# W5500_ETH-SPI.net
KiCad netlist of a schematic drawn in Altium Designer
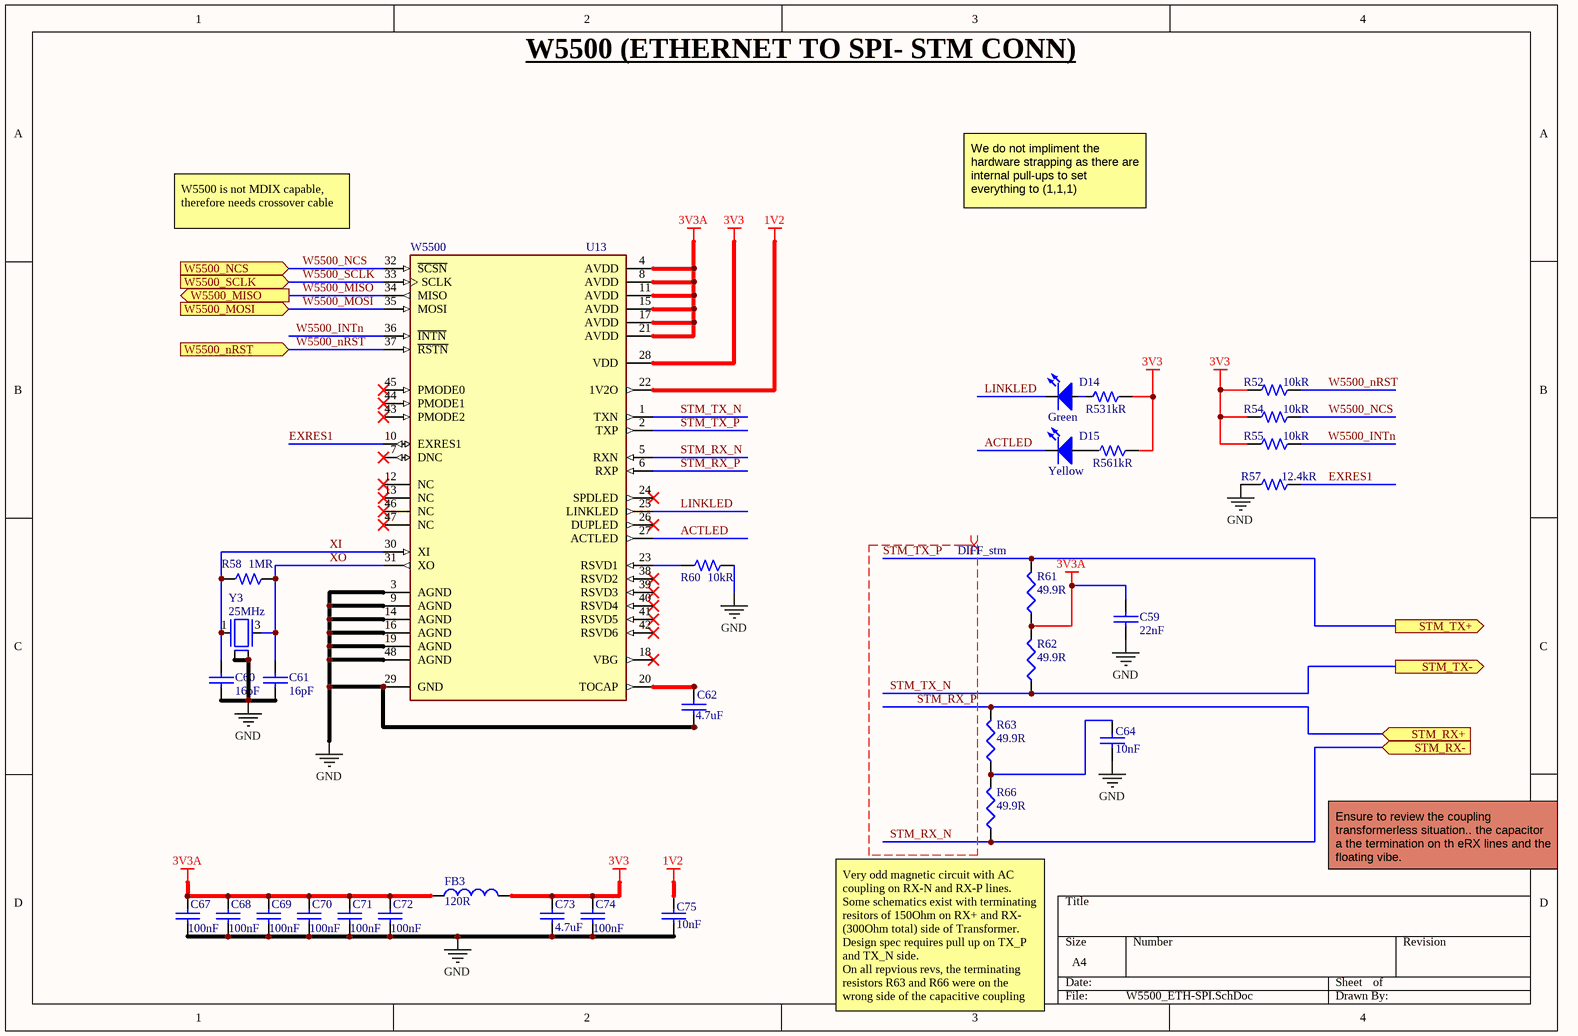
[diagram p0: W5500_ETH-SPI.SchDoc]

(export (version "E")
  (design (tool "Eeschema 10.0.6"))
  (components
    (comp (ref "C59")
      (value "Capacitor")
      (footprint "CAP0402")
      (fields (field (name "CAPACITANCE") "22nF"))
      (libsource (lib "") (part "Capacitor_1"))
    )
    (comp (ref "C60")
      (value "Capacitor")
      (footprint "CAP0402")
      (fields (field (name "CAPACITANCE") "16pF"))
      (libsource (lib "BPL-ShematicLibrary") (part "Capacitor"))
    )
    (comp (ref "C61")
      (value "Capacitor")
      (footprint "CAP0402")
      (fields (field (name "CAPACITANCE") "16pF"))
      (libsource (lib "BPL-ShematicLibrary") (part "Capacitor"))
    )
    (comp (ref "C62")
      (value "Capacitor")
      (footprint "CAP0402")
      (fields (field (name "CAPACITANCE") "4.7uF"))
      (libsource (lib "BPL-ShematicLibrary") (part "Capacitor"))
    )
    (comp (ref "C64")
      (value "Capacitor")
      (footprint "CAP0402")
      (fields (field (name "CAPACITANCE") "10nF"))
      (libsource (lib "") (part "Capacitor_1"))
    )
    (comp (ref "C67")
      (value "Capacitor")
      (footprint "CAP0402")
      (fields
        (field (name "MANUFACTURER") "TDK")
        (field (name "MANUFACTURER PART NUMBER") "CGA2B3X7R1H104K050BB")
        (field (name "CAPACITANCE") "100nF")
        (field (name "TOLERANCE") "10%")
      )
      (libsource (lib "BPL-ShematicLibrary") (part "Capacitor"))
    )
    (comp (ref "C68")
      (value "Capacitor")
      (footprint "CAP0402")
      (fields
        (field (name "MANUFACTURER") "TDK")
        (field (name "MANUFACTURER PART NUMBER") "CGA2B3X7R1H104K050BB")
        (field (name "CAPACITANCE") "100nF")
        (field (name "TOLERANCE") "10%")
      )
      (libsource (lib "BPL-ShematicLibrary") (part "Capacitor"))
    )
    (comp (ref "C69")
      (value "Capacitor")
      (footprint "CAP0402")
      (fields
        (field (name "MANUFACTURER") "TDK")
        (field (name "MANUFACTURER PART NUMBER") "CGA2B3X7R1H104K050BB")
        (field (name "CAPACITANCE") "100nF")
        (field (name "TOLERANCE") "10%")
      )
      (libsource (lib "BPL-ShematicLibrary") (part "Capacitor"))
    )
    (comp (ref "C70")
      (value "Capacitor")
      (footprint "CAP0402")
      (fields
        (field (name "MANUFACTURER") "TDK")
        (field (name "MANUFACTURER PART NUMBER") "CGA2B3X7R1H104K050BB")
        (field (name "CAPACITANCE") "100nF")
        (field (name "TOLERANCE") "10%")
      )
      (libsource (lib "BPL-ShematicLibrary") (part "Capacitor"))
    )
    (comp (ref "C71")
      (value "Capacitor")
      (footprint "CAP0402")
      (fields
        (field (name "MANUFACTURER") "TDK")
        (field (name "MANUFACTURER PART NUMBER") "CGA2B3X7R1H104K050BB")
        (field (name "CAPACITANCE") "100nF")
        (field (name "TOLERANCE") "10%")
      )
      (libsource (lib "BPL-ShematicLibrary") (part "Capacitor"))
    )
    (comp (ref "C72")
      (value "Capacitor")
      (footprint "CAP0402")
      (fields
        (field (name "MANUFACTURER") "TDK")
        (field (name "MANUFACTURER PART NUMBER") "CGA2B3X7R1H104K050BB")
        (field (name "CAPACITANCE") "100nF")
        (field (name "TOLERANCE") "10%")
      )
      (libsource (lib "BPL-ShematicLibrary") (part "Capacitor"))
    )
    (comp (ref "C73")
      (value "Capacitor")
      (footprint "CAP0402")
      (fields (field (name "CAPACITANCE") "4.7uF"))
      (libsource (lib "BPL-ShematicLibrary") (part "Capacitor"))
    )
    (comp (ref "C74")
      (value "Capacitor")
      (footprint "CAP0402")
      (fields
        (field (name "MANUFACTURER") "TDK")
        (field (name "MANUFACTURER PART NUMBER") "CGA2B3X7R1H104K050BB")
        (field (name "CAPACITANCE") "100nF")
        (field (name "TOLERANCE") "10%")
      )
      (libsource (lib "BPL-ShematicLibrary") (part "Capacitor"))
    )
    (comp (ref "C75")
      (value "Capacitor")
      (footprint "CAP0402")
      (fields (field (name "CAPACITANCE") "10nF"))
      (libsource (lib "") (part "Capacitor_1"))
    )
    (comp (ref "D14")
      (value "LED")
      (footprint "LED-0603-GREEN")
      (fields (field (name "COLOR") "Green"))
      (libsource (lib "BPL-ShematicLibrary") (part "LED"))
    )
    (comp (ref "D15")
      (value "LED")
      (footprint "LED-0603-YELLOW")
      (fields (field (name "COLOR") "Yellow"))
      (libsource (lib "BPL-ShematicLibrary") (part "LED"))
    )
    (comp (ref "FB3")
      (value "Ferrite Bead")
      (footprint "RES0402")
      (fields (field (name "TOLERANCE") "25%") (field (name "IMPEDANCE") "120R"))
      (libsource (lib "BPL-ShematicLibrary") (part "Ferrite Bead"))
    )
    (comp (ref "R52")
      (value "Resistor")
      (footprint "RES0402")
      (fields (field (name "RESISTANCE") "10kR") (field (name "TOLERANCE") "1%"))
      (libsource (lib "BPL-ShematicLibrary") (part "Resistor"))
    )
    (comp (ref "R53")
      (value "Resistor")
      (footprint "RES0402")
      (fields (field (name "TOLERANCE") "5%") (field (name "RESISTANCE") "1kR"))
      (libsource (lib "BPL-ShematicLibrary") (part "Resistor"))
    )
    (comp (ref "R54")
      (value "Resistor")
      (footprint "RES0402")
      (fields (field (name "RESISTANCE") "10kR") (field (name "TOLERANCE") "1%"))
      (libsource (lib "BPL-ShematicLibrary") (part "Resistor"))
    )
    (comp (ref "R55")
      (value "Resistor")
      (footprint "RES0402")
      (fields (field (name "RESISTANCE") "10kR") (field (name "TOLERANCE") "1%"))
      (libsource (lib "BPL-ShematicLibrary") (part "Resistor"))
    )
    (comp (ref "R56")
      (value "Resistor")
      (footprint "RES0402")
      (fields (field (name "TOLERANCE") "5%") (field (name "RESISTANCE") "1kR"))
      (libsource (lib "BPL-ShematicLibrary") (part "Resistor"))
    )
    (comp (ref "R57")
      (value "Resistor")
      (footprint "RES0402")
      (fields (field (name "RESISTANCE") "12.4kR") (field (name "TOLERANCE") "0.1%"))
      (libsource (lib "BPL-ShematicLibrary") (part "Resistor"))
    )
    (comp (ref "R58")
      (value "Resistor")
      (footprint "RES0402")
      (fields (field (name "RESISTANCE") "1MR") (field (name "TOLERANCE") "1%"))
      (libsource (lib "BPL-ShematicLibrary") (part "Resistor"))
    )
    (comp (ref "R60")
      (value "Resistor")
      (footprint "RES0402")
      (fields (field (name "RESISTANCE") "10kR") (field (name "TOLERANCE") "1%"))
      (libsource (lib "BPL-ShematicLibrary") (part "Resistor"))
    )
    (comp (ref "R61")
      (value "Res")
      (footprint "RES0402")
      (description "Resistor")
      (fields
        (field (name "MANUFACTURER") "Yageo")
        (field (name "MANUFACTURER PART NUMBER") "RC0402FR-0749R9L")
        (field (name "RESISTANCE") "49.9R")
      )
      (libsource (lib "") (part "Resistor_1"))
    )
    (comp (ref "R62")
      (value "Res")
      (footprint "RES0402")
      (description "Resistor")
      (fields
        (field (name "MANUFACTURER") "Yageo")
        (field (name "MANUFACTURER PART NUMBER") "RC0402FR-0749R9L")
        (field (name "RESISTANCE") "49.9R")
      )
      (libsource (lib "") (part "Resistor_1"))
    )
    (comp (ref "R63")
      (value "Res")
      (footprint "RES0402")
      (description "Resistor")
      (fields
        (field (name "MANUFACTURER") "Yageo")
        (field (name "MANUFACTURER PART NUMBER") "RC0402FR-0749R9L")
        (field (name "RESISTANCE") "49.9R")
      )
      (libsource (lib "") (part "Resistor_1"))
    )
    (comp (ref "R66")
      (value "Res")
      (footprint "RES0402")
      (description "Resistor")
      (fields
        (field (name "MANUFACTURER") "Yageo")
        (field (name "MANUFACTURER PART NUMBER") "RC0402FR-0749R9L")
        (field (name "RESISTANCE") "49.9R")
      )
      (libsource (lib "") (part "Resistor_1"))
    )
    (comp (ref "U13")
      (value "W5500_LQFP48")
      (footprint "LQFP-48, 7x7mm, 0.5mm pitch")
      (description "Ethernet to SPI MCU converter. Onboard TCP handling")
      (fields (field (name "MANUFACTURER PART NUMBER 1") "W5500"))
      (libsource (lib "BPL-ShematicLibrary") (part "W5500_LQFP48"))
    )
    (comp (ref "Y3")
      (value "Crystal_4Pin_ABM8G")
      (footprint "CRYSTAL_ABM8G")
      (fields (field (name "TOLERANCE") "30ppm") (field (name "FREQUENCY") "25MHz"))
      (libsource (lib "BPL-ShematicLibrary") (part "Crystal_4Pin_ABM8G"))
    )
  )
  (nets
    (net (code "1") (name "/ACTLED") (class "Default")
      (node (ref "D15") (pin "1") (pinfunction "1_1") (pintype "passive"))
      (node (ref "U13") (pin "27") (pinfunction "ACTLED_27") (pintype "output"))
    )
    (net (code "2") (name "/EXRES1") (class "Default")
      (node (ref "R57") (pin "1") (pinfunction "1_1") (pintype "passive"))
      (node (ref "U13") (pin "10") (pinfunction "EXRES1_10") (pintype "bidirectional"))
    )
    (net (code "3") (name "/LINKLED") (class "Default")
      (node (ref "D14") (pin "1") (pinfunction "1_1") (pintype "passive"))
      (node (ref "U13") (pin "25") (pinfunction "LINKLED_25") (pintype "output"))
    )
    (net (code "4") (name "/STM_RX_N") (class "Default")
      (node (ref "R66") (pin "1") (pinfunction "1_1") (pintype "passive"))
      (node (ref "U13") (pin "5") (pinfunction "RXN_5") (pintype "input"))
    )
    (net (code "5") (name "/STM_RX_P") (class "Default")
      (node (ref "R63") (pin "2") (pinfunction "2_2") (pintype "passive"))
      (node (ref "U13") (pin "6") (pinfunction "RXP_6") (pintype "input"))
    )
    (net (code "6") (name "/STM_TX_N") (class "Default")
      (node (ref "R62") (pin "1") (pinfunction "1_1") (pintype "passive"))
      (node (ref "U13") (pin "1") (pinfunction "TXN_1") (pintype "output"))
    )
    (net (code "7") (name "/STM_TX_P") (class "Default")
      (node (ref "R61") (pin "2") (pinfunction "2_2") (pintype "passive"))
      (node (ref "U13") (pin "2") (pinfunction "TXP_2") (pintype "output"))
    )
    (net (code "8") (name "/W5500_INTn") (class "Default")
      (node (ref "R55") (pin "1") (pinfunction "1_1") (pintype "passive"))
      (node (ref "U13") (pin "36") (pinfunction "~{INTN}_36") (pintype "input"))
    )
    (net (code "9") (name "/W5500_MISO") (class "Default")
      (node (ref "U13") (pin "34") (pinfunction "MISO_34") (pintype "output"))
    )
    (net (code "10") (name "/W5500_MOSI") (class "Default")
      (node (ref "U13") (pin "35") (pinfunction "MOSI_35") (pintype "input"))
    )
    (net (code "11") (name "/W5500_NCS") (class "Default")
      (node (ref "R54") (pin "1") (pinfunction "1_1") (pintype "passive"))
      (node (ref "U13") (pin "32") (pinfunction "~{SCSN}_32") (pintype "input"))
    )
    (net (code "12") (name "/W5500_SCLK") (class "Default")
      (node (ref "U13") (pin "33") (pinfunction "SCLK_33") (pintype "input"))
    )
    (net (code "13") (name "/W5500_nRST") (class "Default")
      (node (ref "R52") (pin "1") (pinfunction "1_1") (pintype "passive"))
      (node (ref "U13") (pin "37") (pinfunction "~{RSTN}_37") (pintype "input"))
    )
    (net (code "14") (name "/XI") (class "Default")
      (node (ref "C60") (pin "2") (pinfunction "2_2") (pintype "passive"))
      (node (ref "R58") (pin "1") (pinfunction "1_1") (pintype "passive"))
      (node (ref "U13") (pin "30") (pinfunction "XI_30") (pintype "input"))
      (node (ref "Y3") (pin "1") (pinfunction "Osc1_1") (pintype "passive"))
    )
    (net (code "15") (name "/XO") (class "Default")
      (node (ref "C61") (pin "2") (pinfunction "2_2") (pintype "passive"))
      (node (ref "R58") (pin "2") (pinfunction "2_2") (pintype "passive"))
      (node (ref "U13") (pin "31") (pinfunction "XO_31") (pintype "output"))
      (node (ref "Y3") (pin "3") (pinfunction "Osc2_3") (pintype "passive"))
    )
    (net (code "16") (name "1V2") (class "Default")
      (node (ref "C75") (pin "1") (pinfunction "1_1") (pintype "passive"))
      (node (ref "U13") (pin "22") (pinfunction "1V2O_22") (pintype "output"))
    )
    (net (code "17") (name "3V3") (class "Default")
      (node (ref "C73") (pin "1") (pinfunction "1_1") (pintype "passive"))
      (node (ref "C74") (pin "1") (pinfunction "1_1") (pintype "passive"))
      (node (ref "FB3") (pin "2") (pinfunction "2_2") (pintype "passive"))
      (node (ref "R52") (pin "2") (pinfunction "2_2") (pintype "passive"))
      (node (ref "R53") (pin "2") (pinfunction "2_2") (pintype "passive"))
      (node (ref "R54") (pin "2") (pinfunction "2_2") (pintype "passive"))
      (node (ref "R55") (pin "2") (pinfunction "2_2") (pintype "passive"))
      (node (ref "R56") (pin "2") (pinfunction "2_2") (pintype "passive"))
      (node (ref "U13") (pin "28") (pinfunction "VDD_28") (pintype "power_in"))
    )
    (net (code "18") (name "3V3A") (class "Default")
      (node (ref "C59") (pin "1") (pinfunction "1_1") (pintype "passive"))
      (node (ref "C67") (pin "1") (pinfunction "1_1") (pintype "passive"))
      (node (ref "C68") (pin "1") (pinfunction "1_1") (pintype "passive"))
      (node (ref "C69") (pin "1") (pinfunction "1_1") (pintype "passive"))
      (node (ref "C70") (pin "1") (pinfunction "1_1") (pintype "passive"))
      (node (ref "C71") (pin "1") (pinfunction "1_1") (pintype "passive"))
      (node (ref "C72") (pin "1") (pinfunction "1_1") (pintype "passive"))
      (node (ref "FB3") (pin "1") (pinfunction "1_1") (pintype "passive"))
      (node (ref "R61") (pin "1") (pinfunction "1_1") (pintype "passive"))
      (node (ref "R62") (pin "2") (pinfunction "2_2") (pintype "passive"))
      (node (ref "U13") (pin "11") (pinfunction "AVDD_11") (pintype "power_in"))
      (node (ref "U13") (pin "15") (pinfunction "AVDD_15") (pintype "power_in"))
      (node (ref "U13") (pin "17") (pinfunction "AVDD_17") (pintype "power_in"))
      (node (ref "U13") (pin "21") (pinfunction "AVDD_21") (pintype "power_in"))
      (node (ref "U13") (pin "4") (pinfunction "AVDD_4") (pintype "power_in"))
      (node (ref "U13") (pin "8") (pinfunction "AVDD_8") (pintype "power_in"))
    )
    (net (code "19") (name "GND") (class "Default")
      (node (ref "C59") (pin "2") (pinfunction "2_2") (pintype "passive"))
      (node (ref "C60") (pin "1") (pinfunction "1_1") (pintype "passive"))
      (node (ref "C61") (pin "1") (pinfunction "1_1") (pintype "passive"))
      (node (ref "C62") (pin "2") (pinfunction "2_2") (pintype "passive"))
      (node (ref "C64") (pin "2") (pinfunction "2_2") (pintype "passive"))
      (node (ref "C67") (pin "2") (pinfunction "2_2") (pintype "passive"))
      (node (ref "C68") (pin "2") (pinfunction "2_2") (pintype "passive"))
      (node (ref "C69") (pin "2") (pinfunction "2_2") (pintype "passive"))
      (node (ref "C70") (pin "2") (pinfunction "2_2") (pintype "passive"))
      (node (ref "C71") (pin "2") (pinfunction "2_2") (pintype "passive"))
      (node (ref "C72") (pin "2") (pinfunction "2_2") (pintype "passive"))
      (node (ref "C73") (pin "2") (pinfunction "2_2") (pintype "passive"))
      (node (ref "C74") (pin "2") (pinfunction "2_2") (pintype "passive"))
      (node (ref "C75") (pin "2") (pinfunction "2_2") (pintype "passive"))
      (node (ref "R57") (pin "2") (pinfunction "2_2") (pintype "passive"))
      (node (ref "R60") (pin "1") (pinfunction "1_1") (pintype "passive"))
      (node (ref "U13") (pin "14") (pinfunction "AGND_14") (pintype "power_in"))
      (node (ref "U13") (pin "16") (pinfunction "AGND_16") (pintype "power_in"))
      (node (ref "U13") (pin "19") (pinfunction "AGND_19") (pintype "power_in"))
      (node (ref "U13") (pin "29") (pinfunction "GND_29") (pintype "passive"))
      (node (ref "U13") (pin "3") (pinfunction "AGND_3") (pintype "power_in"))
      (node (ref "U13") (pin "48") (pinfunction "AGND_48") (pintype "power_in"))
      (node (ref "U13") (pin "9") (pinfunction "AGND_9") (pintype "power_in"))
      (node (ref "Y3") (pin "2") (pinfunction "GND_2") (pintype "power_in"))
      (node (ref "Y3") (pin "4") (pinfunction "GND_4") (pintype "power_in"))
    )
    (net (code "20") (name "Net-(C64-Pad1)") (class "Default")
      (node (ref "C64") (pin "1") (pinfunction "1_1") (pintype "passive"))
      (node (ref "R63") (pin "1") (pinfunction "1_1") (pintype "passive"))
      (node (ref "R66") (pin "2") (pinfunction "2_2") (pintype "passive"))
    )
    (net (code "21") (name "Net-(D14-Pad2)") (class "Default")
      (node (ref "D14") (pin "2") (pinfunction "2_2") (pintype "passive"))
      (node (ref "R53") (pin "1") (pinfunction "1_1") (pintype "passive"))
    )
    (net (code "22") (name "Net-(D15-Pad2)") (class "Default")
      (node (ref "D15") (pin "2") (pinfunction "2_2") (pintype "passive"))
      (node (ref "R56") (pin "1") (pinfunction "1_1") (pintype "passive"))
    )
    (net (code "23") (name "Net-(U13-RSVD1)") (class "Default")
      (node (ref "R60") (pin "2") (pinfunction "2_2") (pintype "passive"))
      (node (ref "U13") (pin "23") (pinfunction "RSVD1_23") (pintype "input"))
    )
    (net (code "24") (name "Net-(U13-TOCAP)") (class "Default")
      (node (ref "C62") (pin "1") (pinfunction "1_1") (pintype "passive"))
      (node (ref "U13") (pin "20") (pinfunction "TOCAP_20") (pintype "output"))
    )
    (net (code "25") (name "unconnected-(U13-DNC-Pad7)") (class "Default")
      (node (ref "U13") (pin "7") (pinfunction "DNC_7") (pintype "bidirectional+no_connect"))
    )
    (net (code "26") (name "unconnected-(U13-DUPLED-Pad26)") (class "Default")
      (node (ref "U13") (pin "26") (pinfunction "DUPLED_26") (pintype "output+no_connect"))
    )
    (net (code "27") (name "unconnected-(U13-NC-Pad12)") (class "Default")
      (node (ref "U13") (pin "12") (pinfunction "NC_12") (pintype "passive+no_connect"))
    )
    (net (code "28") (name "unconnected-(U13-NC-Pad13)") (class "Default")
      (node (ref "U13") (pin "13") (pinfunction "NC_13") (pintype "passive+no_connect"))
    )
    (net (code "29") (name "unconnected-(U13-NC-Pad46)") (class "Default")
      (node (ref "U13") (pin "46") (pinfunction "NC_46") (pintype "passive+no_connect"))
    )
    (net (code "30") (name "unconnected-(U13-NC-Pad47)") (class "Default")
      (node (ref "U13") (pin "47") (pinfunction "NC_47") (pintype "passive+no_connect"))
    )
    (net (code "31") (name "unconnected-(U13-PMODE0-Pad45)") (class "Default")
      (node (ref "U13") (pin "45") (pinfunction "PMODE0_45") (pintype "input+no_connect"))
    )
    (net (code "32") (name "unconnected-(U13-PMODE1-Pad44)") (class "Default")
      (node (ref "U13") (pin "44") (pinfunction "PMODE1_44") (pintype "input+no_connect"))
    )
    (net (code "33") (name "unconnected-(U13-PMODE2-Pad43)") (class "Default")
      (node (ref "U13") (pin "43") (pinfunction "PMODE2_43") (pintype "input+no_connect"))
    )
    (net (code "34") (name "unconnected-(U13-RSVD2-Pad38)") (class "Default")
      (node (ref "U13") (pin "38") (pinfunction "RSVD2_38") (pintype "input+no_connect"))
    )
    (net (code "35") (name "unconnected-(U13-RSVD3-Pad39)") (class "Default")
      (node (ref "U13") (pin "39") (pinfunction "RSVD3_39") (pintype "input+no_connect"))
    )
    (net (code "36") (name "unconnected-(U13-RSVD4-Pad40)") (class "Default")
      (node (ref "U13") (pin "40") (pinfunction "RSVD4_40") (pintype "input+no_connect"))
    )
    (net (code "37") (name "unconnected-(U13-RSVD5-Pad41)") (class "Default")
      (node (ref "U13") (pin "41") (pinfunction "RSVD5_41") (pintype "input+no_connect"))
    )
    (net (code "38") (name "unconnected-(U13-RSVD6-Pad42)") (class "Default")
      (node (ref "U13") (pin "42") (pinfunction "RSVD6_42") (pintype "input+no_connect"))
    )
    (net (code "39") (name "unconnected-(U13-SPDLED-Pad24)") (class "Default")
      (node (ref "U13") (pin "24") (pinfunction "SPDLED_24") (pintype "output+no_connect"))
    )
    (net (code "40") (name "unconnected-(U13-VBG-Pad18)") (class "Default")
      (node (ref "U13") (pin "18") (pinfunction "VBG_18") (pintype "output+no_connect"))
    )
  )
)
